# CW308T-FE310-G002.net
KiCad netlist of a schematic drawn in Altium Designer
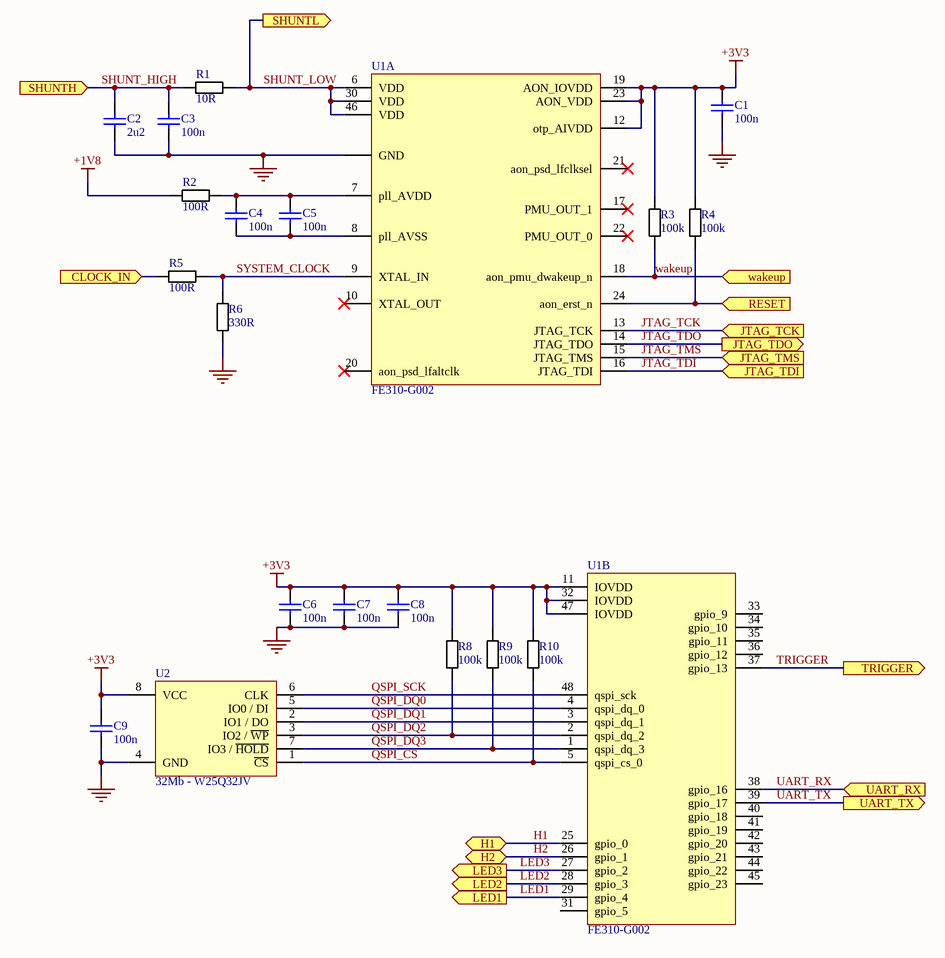
[diagram p0: CW308T-FE310-G002.SchDoc]

(export (version "E")
  (design (tool "Eeschema 10.0.6"))
  (components
    (comp (ref "C1")
      (value "100n")
      (footprint "CAPC0603_M")
      (description "100n, 0603")
      (fields (field (name "PART NUMBER") "CCHIP-100n-0603"))
      (libsource (lib "NewAE_AltiumLib") (part "CAP"))
    )
    (comp (ref "C2")
      (value "2u2")
      (footprint "CAPC0603_M")
      (description "2u2, 0603")
      (fields (field (name "PART NUMBER") "CCHIP-2u2-0603"))
      (libsource (lib "NewAE_AltiumLib") (part "CAP"))
    )
    (comp (ref "C3")
      (value "100n")
      (footprint "CAPC0603_M")
      (description "100n, 0603")
      (fields (field (name "PART NUMBER") "CCHIP-100n-0603"))
      (libsource (lib "NewAE_AltiumLib") (part "CAP"))
    )
    (comp (ref "C4")
      (value "100n")
      (footprint "CAPC0603_M")
      (description "100n, 0603")
      (fields (field (name "PART NUMBER") "CCHIP-100n-0603"))
      (libsource (lib "NewAE_AltiumLib") (part "CAP"))
    )
    (comp (ref "C5")
      (value "100n")
      (footprint "CAPC0603_M")
      (description "100n, 0603")
      (fields (field (name "PART NUMBER") "CCHIP-100n-0603"))
      (libsource (lib "NewAE_AltiumLib") (part "CAP"))
    )
    (comp (ref "C6")
      (value "100n")
      (footprint "CAPC0603_M")
      (description "100n, 0603")
      (fields (field (name "PART NUMBER") "CCHIP-100n-0603"))
      (libsource (lib "NewAE_AltiumLib") (part "CAP"))
    )
    (comp (ref "C7")
      (value "100n")
      (footprint "CAPC0603_M")
      (description "100n, 0603")
      (fields (field (name "PART NUMBER") "CCHIP-100n-0603"))
      (libsource (lib "NewAE_AltiumLib") (part "CAP"))
    )
    (comp (ref "C8")
      (value "100n")
      (footprint "CAPC0603_M")
      (description "100n, 0603")
      (fields (field (name "PART NUMBER") "CCHIP-100n-0603"))
      (libsource (lib "NewAE_AltiumLib") (part "CAP"))
    )
    (comp (ref "C9")
      (value "100n")
      (footprint "CAPC0603_M")
      (description "100n, 0603")
      (fields (field (name "PART NUMBER") "CCHIP-100n-0603"))
      (libsource (lib "NewAE_AltiumLib") (part "CAP"))
    )
    (comp (ref "R1")
      (value "10R")
      (footprint "RESC1608X55N")
      (description "10R res, 0603, 1%, 1/10W")
      (fields (field (name "PART NUMBER") "RCHIP-10R-0603") (field (name "TOLERANCE") "1%"))
      (libsource (lib "NewAE_AltiumLib") (part "RES-EU"))
    )
    (comp (ref "R2")
      (value "100R")
      (footprint "RESC1608X55N")
      (description "100R res, 0603, 1%, 1/10W")
      (fields (field (name "PART NUMBER") "RCHIP-100R-0603") (field (name "TOLERANCE") "1%"))
      (libsource (lib "NewAE_AltiumLib") (part "RES-EU"))
    )
    (comp (ref "R3")
      (value "100k")
      (footprint "RESC1608X55N")
      (description "100k res, 0603, 1%, 1/10W")
      (fields (field (name "PART NUMBER") "RCHIP-100K-0603") (field (name "TOLERANCE") "1%"))
      (libsource (lib "") (part "RES-EU_1"))
    )
    (comp (ref "R4")
      (value "100k")
      (footprint "RESC1608X55N")
      (description "100k res, 0603, 1%, 1/10W")
      (fields (field (name "PART NUMBER") "RCHIP-100K-0603") (field (name "TOLERANCE") "1%"))
      (libsource (lib "") (part "RES-EU_1"))
    )
    (comp (ref "R5")
      (value "100R")
      (footprint "RESC1608X55N")
      (description "100R res, 0603, 1%, 1/10W")
      (fields (field (name "PART NUMBER") "RCHIP-100R-0603") (field (name "TOLERANCE") "1%"))
      (libsource (lib "NewAE_AltiumLib") (part "RES-EU"))
    )
    (comp (ref "R6")
      (value "330R")
      (footprint "RESC1608X55N")
      (description "330R res, 0603, 1%, 1/10W")
      (fields (field (name "PART NUMBER") "RCHIP-330R-0603") (field (name "TOLERANCE") "1%"))
      (libsource (lib "") (part "RES-EU_1"))
    )
    (comp (ref "R8")
      (value "100k")
      (footprint "RESC1608X55N")
      (description "100k res, 0603, 1%, 1/10W")
      (fields (field (name "PART NUMBER") "RCHIP-100K-0603") (field (name "TOLERANCE") "1%"))
      (libsource (lib "") (part "RES-EU_1"))
    )
    (comp (ref "R9")
      (value "100k")
      (footprint "RESC1608X55N")
      (description "100k res, 0603, 1%, 1/10W")
      (fields (field (name "PART NUMBER") "RCHIP-100K-0603") (field (name "TOLERANCE") "1%"))
      (libsource (lib "") (part "RES-EU_1"))
    )
    (comp (ref "R10")
      (value "100k")
      (footprint "RESC1608X55N")
      (description "100k res, 0603, 1%, 1/10W")
      (fields (field (name "PART NUMBER") "RCHIP-100K-0603") (field (name "TOLERANCE") "1%"))
      (libsource (lib "") (part "RES-EU_1"))
    )
    (comp (ref "U1")
      (value "FE310-G002")
      (footprint "QFN40P600X600X95_HS-49N")
      (description "RISC-V FREEDOM SoC")
      (libsource (lib "NewAE_AltiumLib") (part "FE310-G002"))
    )
    (comp (ref "U2")
      (value "32Mb - W25Q32JV")
      (footprint "SOIC127P790X216-8N")
      (description "IC FLASH 32M SPI 133MHZ 8SOIC")
      (fields (field (name "PART NUMBER") "QSPI-FLASH-32M-32Mb"))
      (libsource (lib "NewAE_AltiumLib") (part "W25Q32JV"))
    )
  )
  (nets
    (net (code "1") (name "+1V8") (class "Default")
      (node (ref "R2") (pin "1") (pinfunction "1_1") (pintype "passive"))
    )
    (net (code "2") (name "+3V3") (class "Default")
      (node (ref "C1") (pin "1") (pinfunction "1_1") (pintype "passive"))
      (node (ref "C6") (pin "1") (pinfunction "1_1") (pintype "passive"))
      (node (ref "C7") (pin "1") (pinfunction "1_1") (pintype "passive"))
      (node (ref "C8") (pin "1") (pinfunction "1_1") (pintype "passive"))
      (node (ref "C9") (pin "1") (pinfunction "1_1") (pintype "passive"))
      (node (ref "R10") (pin "1") (pinfunction "1_1") (pintype "passive"))
      (node (ref "R3") (pin "1") (pinfunction "1_1") (pintype "passive"))
      (node (ref "R4") (pin "1") (pinfunction "1_1") (pintype "passive"))
      (node (ref "R8") (pin "1") (pinfunction "1_1") (pintype "passive"))
      (node (ref "R9") (pin "1") (pinfunction "1_1") (pintype "passive"))
      (node (ref "U1") (pin "11") (pinfunction "IOVDD_11") (pintype "passive"))
      (node (ref "U1") (pin "12") (pinfunction "otp_AIVDD_12") (pintype "passive"))
      (node (ref "U1") (pin "19") (pinfunction "AON_IOVDD_19") (pintype "passive"))
      (node (ref "U1") (pin "23") (pinfunction "AON_VDD_23") (pintype "passive"))
      (node (ref "U1") (pin "32") (pinfunction "IOVDD_32") (pintype "passive"))
      (node (ref "U1") (pin "47") (pinfunction "IOVDD_47") (pintype "passive"))
      (node (ref "U2") (pin "8") (pinfunction "VCC_8") (pintype "passive"))
    )
    (net (code "3") (name "/CLOCK_IN") (class "Default")
      (node (ref "R5") (pin "1") (pinfunction "1_1") (pintype "passive"))
    )
    (net (code "4") (name "/H1") (class "Default")
      (node (ref "U1") (pin "25") (pinfunction "gpio_0_25") (pintype "passive"))
    )
    (net (code "5") (name "/H2") (class "Default")
      (node (ref "U1") (pin "26") (pinfunction "gpio_1_26") (pintype "passive"))
    )
    (net (code "6") (name "/JTAG_TCK") (class "Default")
      (node (ref "U1") (pin "13") (pinfunction "JTAG_TCK_13") (pintype "passive"))
    )
    (net (code "7") (name "/JTAG_TDI") (class "Default")
      (node (ref "U1") (pin "16") (pinfunction "JTAG_TDI_16") (pintype "passive"))
    )
    (net (code "8") (name "/JTAG_TDO") (class "Default")
      (node (ref "U1") (pin "14") (pinfunction "JTAG_TDO_14") (pintype "passive"))
    )
    (net (code "9") (name "/JTAG_TMS") (class "Default")
      (node (ref "U1") (pin "15") (pinfunction "JTAG_TMS_15") (pintype "passive"))
    )
    (net (code "10") (name "/LED1") (class "Default")
      (node (ref "U1") (pin "29") (pinfunction "gpio_4_29") (pintype "passive"))
    )
    (net (code "11") (name "/LED2") (class "Default")
      (node (ref "U1") (pin "28") (pinfunction "gpio_3_28") (pintype "passive"))
    )
    (net (code "12") (name "/LED3") (class "Default")
      (node (ref "U1") (pin "27") (pinfunction "gpio_2_27") (pintype "passive"))
    )
    (net (code "13") (name "/QSPI_CS") (class "Default")
      (node (ref "R10") (pin "2") (pinfunction "2_2") (pintype "passive"))
      (node (ref "U1") (pin "5") (pinfunction "qspi_cs_0_5") (pintype "passive"))
      (node (ref "U2") (pin "1") (pinfunction "~{CS}_1") (pintype "passive"))
    )
    (net (code "14") (name "/QSPI_DQ0") (class "Default")
      (node (ref "U1") (pin "4") (pinfunction "qspi_dq_0_4") (pintype "passive"))
      (node (ref "U2") (pin "5") (pinfunction "IO0_/_DI_5") (pintype "passive"))
    )
    (net (code "15") (name "/QSPI_DQ1") (class "Default")
      (node (ref "U1") (pin "3") (pinfunction "qspi_dq_1_3") (pintype "passive"))
      (node (ref "U2") (pin "2") (pinfunction "IO1_/_DO_2") (pintype "passive"))
    )
    (net (code "16") (name "/QSPI_DQ2") (class "Default")
      (node (ref "R8") (pin "2") (pinfunction "2_2") (pintype "passive"))
      (node (ref "U1") (pin "2") (pinfunction "qspi_dq_2_2") (pintype "passive"))
      (node (ref "U2") (pin "3") (pinfunction "IO2_/_~{WP}_3") (pintype "passive"))
    )
    (net (code "17") (name "/QSPI_DQ3") (class "Default")
      (node (ref "R9") (pin "2") (pinfunction "2_2") (pintype "passive"))
      (node (ref "U1") (pin "1") (pinfunction "qspi_dq_3_1") (pintype "passive"))
      (node (ref "U2") (pin "7") (pinfunction "IO3_/_~{HOLD}_7") (pintype "passive"))
    )
    (net (code "18") (name "/QSPI_SCK") (class "Default")
      (node (ref "U1") (pin "48") (pinfunction "qspi_sck_48") (pintype "passive"))
      (node (ref "U2") (pin "6") (pinfunction "CLK_6") (pintype "passive"))
    )
    (net (code "19") (name "/RESET") (class "Default")
      (node (ref "R4") (pin "2") (pinfunction "2_2") (pintype "passive"))
      (node (ref "U1") (pin "24") (pinfunction "aon_erst_n_24") (pintype "passive"))
    )
    (net (code "20") (name "/SHUNT_HIGH") (class "Default")
      (node (ref "C2") (pin "1") (pinfunction "1_1") (pintype "passive"))
      (node (ref "C3") (pin "1") (pinfunction "1_1") (pintype "passive"))
      (node (ref "R1") (pin "1") (pinfunction "1_1") (pintype "passive"))
    )
    (net (code "21") (name "/SHUNT_LOW") (class "Default")
      (node (ref "R1") (pin "2") (pinfunction "2_2") (pintype "passive"))
      (node (ref "U1") (pin "30") (pinfunction "VDD_30") (pintype "passive"))
      (node (ref "U1") (pin "46") (pinfunction "VDD_46") (pintype "passive"))
      (node (ref "U1") (pin "6") (pinfunction "VDD_6") (pintype "passive"))
    )
    (net (code "22") (name "/SYSTEM_CLOCK") (class "Default")
      (node (ref "R5") (pin "2") (pinfunction "2_2") (pintype "passive"))
      (node (ref "R6") (pin "1") (pinfunction "1_1") (pintype "passive"))
      (node (ref "U1") (pin "9") (pinfunction "XTAL_IN_9") (pintype "passive"))
    )
    (net (code "23") (name "/TRIGGER") (class "Default")
      (node (ref "U1") (pin "37") (pinfunction "gpio_13_37") (pintype "passive"))
    )
    (net (code "24") (name "/UART_RX") (class "Default")
      (node (ref "U1") (pin "38") (pinfunction "gpio_16_38") (pintype "passive"))
    )
    (net (code "25") (name "/UART_TX") (class "Default")
      (node (ref "U1") (pin "39") (pinfunction "gpio_17_39") (pintype "passive"))
    )
    (net (code "26") (name "/wakeup") (class "Default")
      (node (ref "R3") (pin "2") (pinfunction "2_2") (pintype "passive"))
      (node (ref "U1") (pin "18") (pinfunction "aon_pmu_dwakeup_n_18") (pintype "passive"))
    )
    (net (code "27") (name "GND") (class "Default")
      (node (ref "C1") (pin "2") (pinfunction "2_2") (pintype "passive"))
      (node (ref "C2") (pin "2") (pinfunction "2_2") (pintype "passive"))
      (node (ref "C3") (pin "2") (pinfunction "2_2") (pintype "passive"))
      (node (ref "C6") (pin "2") (pinfunction "2_2") (pintype "passive"))
      (node (ref "C7") (pin "2") (pinfunction "2_2") (pintype "passive"))
      (node (ref "C8") (pin "2") (pinfunction "2_2") (pintype "passive"))
      (node (ref "C9") (pin "2") (pinfunction "2_2") (pintype "passive"))
      (node (ref "R6") (pin "2") (pinfunction "2_2") (pintype "passive"))
      (node (ref "U1") (pin "PAD") (pinfunction "GND_PAD") (pintype "passive"))
      (node (ref "U2") (pin "4") (pinfunction "GND_4") (pintype "passive"))
    )
    (net (code "28") (name "Net-(U1A-pll_AVDD)") (class "Default")
      (node (ref "C4") (pin "1") (pinfunction "1_1") (pintype "passive"))
      (node (ref "C5") (pin "1") (pinfunction "1_1") (pintype "passive"))
      (node (ref "R2") (pin "2") (pinfunction "2_2") (pintype "passive"))
      (node (ref "U1") (pin "7") (pinfunction "pll_AVDD_7") (pintype "passive"))
    )
    (net (code "29") (name "Net-(U1A-pll_AVSS)") (class "Default")
      (node (ref "C4") (pin "2") (pinfunction "2_2") (pintype "passive"))
      (node (ref "C5") (pin "2") (pinfunction "2_2") (pintype "passive"))
      (node (ref "U1") (pin "8") (pinfunction "pll_AVSS_8") (pintype "passive"))
    )
    (net (code "30") (name "unconnected-(U1A-PMU_OUT_0-Pad22)") (class "Default")
      (node (ref "U1") (pin "22") (pinfunction "PMU_OUT_0_22") (pintype "passive+no_connect"))
    )
    (net (code "31") (name "unconnected-(U1A-PMU_OUT_1-Pad17)") (class "Default")
      (node (ref "U1") (pin "17") (pinfunction "PMU_OUT_1_17") (pintype "passive+no_connect"))
    )
    (net (code "32") (name "unconnected-(U1A-XTAL_OUT-Pad10)") (class "Default")
      (node (ref "U1") (pin "10") (pinfunction "XTAL_OUT_10") (pintype "passive+no_connect"))
    )
    (net (code "33") (name "unconnected-(U1A-aon_psd_lfaltclk-Pad20)") (class "Default")
      (node (ref "U1") (pin "20") (pinfunction "aon_psd_lfaltclk_20") (pintype "passive+no_connect"))
    )
    (net (code "34") (name "unconnected-(U1A-aon_psd_lfclksel-Pad21)") (class "Default")
      (node (ref "U1") (pin "21") (pinfunction "aon_psd_lfclksel_21") (pintype "passive+no_connect"))
    )
    (net (code "35") (name "unconnected-(U1B-gpio_5-Pad31)") (class "Default")
      (node (ref "U1") (pin "31") (pinfunction "gpio_5_31") (pintype "passive"))
    )
    (net (code "36") (name "unconnected-(U1B-gpio_9-Pad33)") (class "Default")
      (node (ref "U1") (pin "33") (pinfunction "gpio_9_33") (pintype "passive"))
    )
    (net (code "37") (name "unconnected-(U1B-gpio_10-Pad34)") (class "Default")
      (node (ref "U1") (pin "34") (pinfunction "gpio_10_34") (pintype "passive"))
    )
    (net (code "38") (name "unconnected-(U1B-gpio_11-Pad35)") (class "Default")
      (node (ref "U1") (pin "35") (pinfunction "gpio_11_35") (pintype "passive"))
    )
    (net (code "39") (name "unconnected-(U1B-gpio_12-Pad36)") (class "Default")
      (node (ref "U1") (pin "36") (pinfunction "gpio_12_36") (pintype "passive"))
    )
    (net (code "40") (name "unconnected-(U1B-gpio_18-Pad40)") (class "Default")
      (node (ref "U1") (pin "40") (pinfunction "gpio_18_40") (pintype "passive"))
    )
    (net (code "41") (name "unconnected-(U1B-gpio_19-Pad41)") (class "Default")
      (node (ref "U1") (pin "41") (pinfunction "gpio_19_41") (pintype "passive"))
    )
    (net (code "42") (name "unconnected-(U1B-gpio_20-Pad42)") (class "Default")
      (node (ref "U1") (pin "42") (pinfunction "gpio_20_42") (pintype "passive"))
    )
    (net (code "43") (name "unconnected-(U1B-gpio_21-Pad43)") (class "Default")
      (node (ref "U1") (pin "43") (pinfunction "gpio_21_43") (pintype "passive"))
    )
    (net (code "44") (name "unconnected-(U1B-gpio_22-Pad44)") (class "Default")
      (node (ref "U1") (pin "44") (pinfunction "gpio_22_44") (pintype "passive"))
    )
    (net (code "45") (name "unconnected-(U1B-gpio_23-Pad45)") (class "Default")
      (node (ref "U1") (pin "45") (pinfunction "gpio_23_45") (pintype "passive"))
    )
  )
)
